# v001.net
KiCad netlist of a schematic drawn in EAGLE
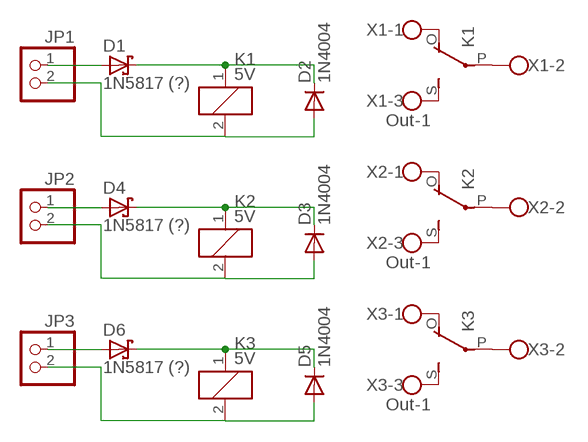
[diagram p0: schematic, sheet 1]

(export (version "E")
  (design (tool "Eeschema 10.0.6"))
  (components
    (comp (ref "D1")
      (value "1N5817 (?)")
      (footprint "eagle-import:DO41-7.6")
      (libsource (lib "eagle-import") (part "1N5817-B"))
    )
    (comp (ref "D2")
      (value "1N4004")
      (footprint "eagle-import:DO41-10")
      (libsource (lib "eagle-import") (part "1N4004"))
    )
    (comp (ref "D3")
      (value "1N4004")
      (footprint "eagle-import:DO41-10")
      (libsource (lib "eagle-import") (part "1N4004"))
    )
    (comp (ref "D4")
      (value "1N5817 (?)")
      (footprint "eagle-import:DO41-7.6")
      (libsource (lib "eagle-import") (part "1N5817-B"))
    )
    (comp (ref "D5")
      (value "1N4004")
      (footprint "eagle-import:DO41-10")
      (libsource (lib "eagle-import") (part "1N4004"))
    )
    (comp (ref "D6")
      (value "1N5817 (?)")
      (footprint "eagle-import:DO41-7.6")
      (libsource (lib "eagle-import") (part "1N5817-B"))
    )
    (comp (ref "JP1")
      (value "PINHD-1X2")
      (footprint "eagle-import:1X02")
      (libsource (lib "eagle-import") (part "PINHD-1X2"))
    )
    (comp (ref "JP2")
      (value "PINHD-1X2")
      (footprint "eagle-import:1X02")
      (libsource (lib "eagle-import") (part "PINHD-1X2"))
    )
    (comp (ref "JP3")
      (value "PINHD-1X2")
      (footprint "eagle-import:1X02")
      (libsource (lib "eagle-import") (part "PINHD-1X2"))
    )
    (comp (ref "K1")
      (value "5V")
      (footprint "eagle-import:G5LE")
      (libsource (lib "eagle-import") (part "G5L"))
    )
    (comp (ref "K2")
      (value "5V")
      (footprint "eagle-import:G5LE")
      (libsource (lib "eagle-import") (part "G5L"))
    )
    (comp (ref "K3")
      (value "5V")
      (footprint "eagle-import:G5LE")
      (libsource (lib "eagle-import") (part "G5L"))
    )
    (comp (ref "X1")
      (value "Out-1")
      (footprint "eagle-import:W237-103")
      (fields (field (name "MPN") "237-103"))
      (libsource (lib "eagle-import") (part "W237-103"))
    )
    (comp (ref "X2")
      (value "Out-1")
      (footprint "eagle-import:W237-103")
      (fields (field (name "MPN") "237-103"))
      (libsource (lib "eagle-import") (part "W237-103"))
    )
    (comp (ref "X3")
      (value "Out-1")
      (footprint "eagle-import:W237-103")
      (fields (field (name "MPN") "237-103"))
      (libsource (lib "eagle-import") (part "W237-103"))
    )
  )
  (nets
    (net (code "1") (name "Net-(D1-PadA)") (class "Default")
      (node (ref "D1") (pin "A") (pinfunction "A_A") (pintype "passive"))
      (node (ref "JP1") (pin "1") (pinfunction "1_1") (pintype "passive"))
    )
    (net (code "2") (name "Net-(D1-PadC)") (class "Default")
      (node (ref "D1") (pin "C") (pinfunction "C_C") (pintype "passive"))
      (node (ref "D2") (pin "C") (pinfunction "C_C") (pintype "passive"))
      (node (ref "K1") (pin "1") (pinfunction "1_1") (pintype "passive"))
    )
    (net (code "3") (name "Net-(D2-PadA)") (class "Default")
      (node (ref "D2") (pin "A") (pinfunction "A_A") (pintype "passive"))
      (node (ref "JP1") (pin "2") (pinfunction "2_2") (pintype "passive"))
      (node (ref "K1") (pin "2") (pinfunction "2_2") (pintype "passive"))
    )
    (net (code "4") (name "Net-(D3-PadA)") (class "Default")
      (node (ref "D3") (pin "A") (pinfunction "A_A") (pintype "passive"))
      (node (ref "JP2") (pin "2") (pinfunction "2_2") (pintype "passive"))
      (node (ref "K2") (pin "2") (pinfunction "2_2") (pintype "passive"))
    )
    (net (code "5") (name "Net-(D3-PadC)") (class "Default")
      (node (ref "D3") (pin "C") (pinfunction "C_C") (pintype "passive"))
      (node (ref "D4") (pin "C") (pinfunction "C_C") (pintype "passive"))
      (node (ref "K2") (pin "1") (pinfunction "1_1") (pintype "passive"))
    )
    (net (code "6") (name "Net-(D4-PadA)") (class "Default")
      (node (ref "D4") (pin "A") (pinfunction "A_A") (pintype "passive"))
      (node (ref "JP2") (pin "1") (pinfunction "1_1") (pintype "passive"))
    )
    (net (code "7") (name "Net-(D5-PadA)") (class "Default")
      (node (ref "D5") (pin "A") (pinfunction "A_A") (pintype "passive"))
      (node (ref "JP3") (pin "2") (pinfunction "2_2") (pintype "passive"))
      (node (ref "K3") (pin "2") (pinfunction "2_2") (pintype "passive"))
    )
    (net (code "8") (name "Net-(D5-PadC)") (class "Default")
      (node (ref "D5") (pin "C") (pinfunction "C_C") (pintype "passive"))
      (node (ref "D6") (pin "C") (pinfunction "C_C") (pintype "passive"))
      (node (ref "K3") (pin "1") (pinfunction "1_1") (pintype "passive"))
    )
    (net (code "9") (name "Net-(D6-PadA)") (class "Default")
      (node (ref "D6") (pin "A") (pinfunction "A_A") (pintype "passive"))
      (node (ref "JP3") (pin "1") (pinfunction "1_1") (pintype "passive"))
    )
    (net (code "10") (name "Net-(X1A-KL)") (class "Default")
      (node (ref "K1") (pin "O") (pinfunction "O_O") (pintype "passive"))
      (node (ref "X1") (pin "1") (pinfunction "KL_1") (pintype "passive"))
    )
    (net (code "11") (name "Net-(X1B-KL)") (class "Default")
      (node (ref "K1") (pin "P") (pinfunction "P_P") (pintype "passive"))
      (node (ref "X1") (pin "2") (pinfunction "KL_2") (pintype "passive"))
    )
    (net (code "12") (name "Net-(X1C-KL)") (class "Default")
      (node (ref "K1") (pin "S") (pinfunction "S_S") (pintype "passive"))
      (node (ref "X1") (pin "3") (pinfunction "KL_3") (pintype "passive"))
    )
    (net (code "13") (name "Net-(X2A-KL)") (class "Default")
      (node (ref "K2") (pin "O") (pinfunction "O_O") (pintype "passive"))
      (node (ref "X2") (pin "1") (pinfunction "KL_1") (pintype "passive"))
    )
    (net (code "14") (name "Net-(X2B-KL)") (class "Default")
      (node (ref "K2") (pin "P") (pinfunction "P_P") (pintype "passive"))
      (node (ref "X2") (pin "2") (pinfunction "KL_2") (pintype "passive"))
    )
    (net (code "15") (name "Net-(X2C-KL)") (class "Default")
      (node (ref "K2") (pin "S") (pinfunction "S_S") (pintype "passive"))
      (node (ref "X2") (pin "3") (pinfunction "KL_3") (pintype "passive"))
    )
    (net (code "16") (name "Net-(X3A-KL)") (class "Default")
      (node (ref "K3") (pin "O") (pinfunction "O_O") (pintype "passive"))
      (node (ref "X3") (pin "1") (pinfunction "KL_1") (pintype "passive"))
    )
    (net (code "17") (name "Net-(X3B-KL)") (class "Default")
      (node (ref "K3") (pin "P") (pinfunction "P_P") (pintype "passive"))
      (node (ref "X3") (pin "2") (pinfunction "KL_2") (pintype "passive"))
    )
    (net (code "18") (name "Net-(X3C-KL)") (class "Default")
      (node (ref "K3") (pin "S") (pinfunction "S_S") (pintype "passive"))
      (node (ref "X3") (pin "3") (pinfunction "KL_3") (pintype "passive"))
    )
  )
)
